# covid-respirator-ProtoB.net
KiCad netlist of a schematic drawn in EAGLE
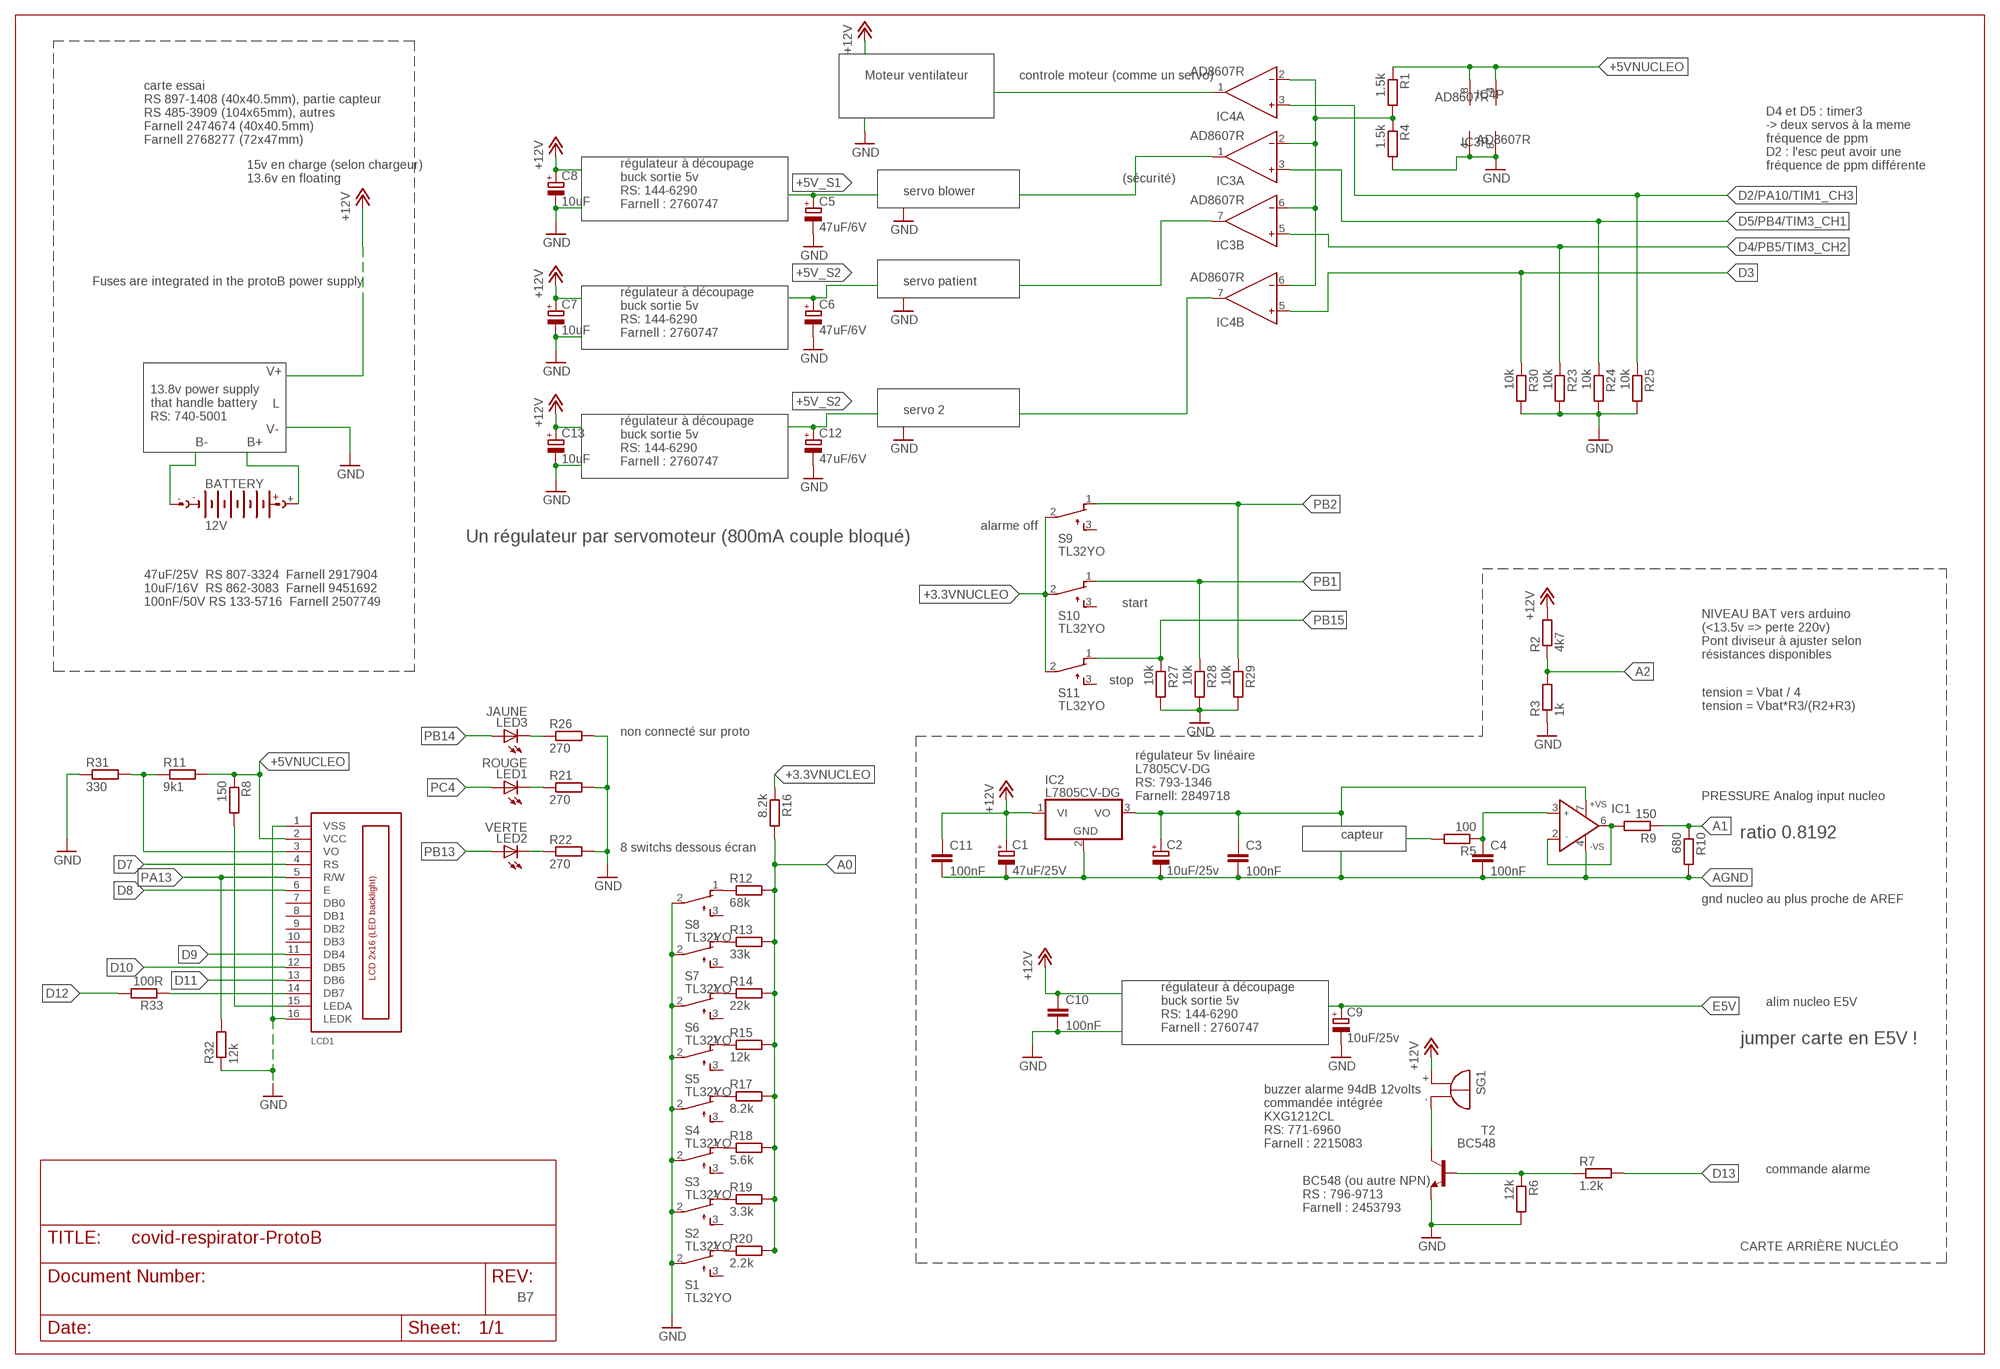
[diagram p0: schematic, sheet 1]

(export (version "E")
  (design (tool "Eeschema 10.0.6"))
  (components
    (comp (ref "BATTERY")
      (value "12V")
      (footprint "eagle-import:AB9V")
      (libsource (lib "eagle-import") (part "AB9V"))
    )
    (comp (ref "C1")
      (value "47uF/25V")
      (footprint "eagle-import:150CLZ-1010")
      (libsource (lib "eagle-import") (part "CPOL-EU150CLZ-1010"))
    )
    (comp (ref "C2")
      (value "10uF/25v")
      (footprint "eagle-import:150CLZ-1010")
      (libsource (lib "eagle-import") (part "CPOL-EU150CLZ-1010"))
    )
    (comp (ref "C3")
      (value "100nF")
      (footprint "eagle-import:C050-050X075")
      (libsource (lib "eagle-import") (part "C-EU050-050X075"))
    )
    (comp (ref "C4")
      (value "100nF")
      (footprint "eagle-import:C050-050X075")
      (libsource (lib "eagle-import") (part "C-EU050-050X075"))
    )
    (comp (ref "C5")
      (value "47uF/6V")
      (footprint "eagle-import:150CLZ-1010")
      (libsource (lib "eagle-import") (part "CPOL-EU150CLZ-1010"))
    )
    (comp (ref "C6")
      (value "47uF/6V")
      (footprint "eagle-import:150CLZ-1010")
      (libsource (lib "eagle-import") (part "CPOL-EU150CLZ-1010"))
    )
    (comp (ref "C7")
      (value "10uF")
      (footprint "eagle-import:150CLZ-1010")
      (libsource (lib "eagle-import") (part "CPOL-EU150CLZ-1010"))
    )
    (comp (ref "C8")
      (value "10uF")
      (footprint "eagle-import:150CLZ-1010")
      (libsource (lib "eagle-import") (part "CPOL-EU150CLZ-1010"))
    )
    (comp (ref "C9")
      (value "10uF/25v")
      (footprint "eagle-import:150CLZ-1010")
      (libsource (lib "eagle-import") (part "CPOL-EU150CLZ-1010"))
    )
    (comp (ref "C10")
      (value "100nF")
      (footprint "eagle-import:C050-050X075")
      (libsource (lib "eagle-import") (part "C-EU050-050X075"))
    )
    (comp (ref "C11")
      (value "100nF")
      (footprint "eagle-import:C050-050X075")
      (libsource (lib "eagle-import") (part "C-EU050-050X075"))
    )
    (comp (ref "C12")
      (value "47uF/6V")
      (footprint "eagle-import:150CLZ-1010")
      (libsource (lib "eagle-import") (part "CPOL-EU150CLZ-1010"))
    )
    (comp (ref "C13")
      (value "10uF")
      (footprint "eagle-import:150CLZ-1010")
      (libsource (lib "eagle-import") (part "CPOL-EU150CLZ-1010"))
    )
    (comp (ref "IC1")
      (value "AD825R")
      (footprint "eagle-import:SO8")
      (fields (field (name "MF") "ALTERA CORPORATION") (field (name "MPN") "AD825ARZ"))
      (libsource (lib "eagle-import") (part "AD825R"))
    )
    (comp (ref "IC2")
      (value "L7805CV-DG")
      (footprint "eagle-import:TO220H")
      (libsource (lib "eagle-import") (part "78T05"))
    )
    (comp (ref "IC3")
      (value "AD8607R")
      (footprint "eagle-import:SO8")
      (fields (field (name "MPN") "AD8607ARMZ-R2"))
      (libsource (lib "eagle-import") (part "AD8607R"))
    )
    (comp (ref "IC4")
      (value "AD8607R")
      (footprint "eagle-import:SO8")
      (fields (field (name "MPN") "AD8607ARMZ-R2"))
      (libsource (lib "eagle-import") (part "AD8607R"))
    )
    (comp (ref "LCD1")
      (value "LCD_2X16_SIL")
      (footprint "eagle-import:HY-1602F")
      (libsource (lib "eagle-import") (part "LCD_2X16_SIL"))
    )
    (comp (ref "LED1")
      (value "ROUGE")
      (footprint "eagle-import:LED3MM")
      (libsource (lib "eagle-import") (part "LED3MM"))
    )
    (comp (ref "LED2")
      (value "VERTE")
      (footprint "eagle-import:LED3MM")
      (libsource (lib "eagle-import") (part "LED3MM"))
    )
    (comp (ref "LED3")
      (value "JAUNE")
      (footprint "eagle-import:LED3MM")
      (libsource (lib "eagle-import") (part "LED3MM"))
    )
    (comp (ref "R1")
      (value "1.5k")
      (footprint "eagle-import:0207_10")
      (libsource (lib "eagle-import") (part "R-EU_0207/10"))
    )
    (comp (ref "R2")
      (value "4k7")
      (footprint "eagle-import:0207_10")
      (libsource (lib "eagle-import") (part "R-EU_0207/10"))
    )
    (comp (ref "R3")
      (value "1k")
      (footprint "eagle-import:0207_10")
      (libsource (lib "eagle-import") (part "R-EU_0207/10"))
    )
    (comp (ref "R4")
      (value "1.5k")
      (footprint "eagle-import:0207_10")
      (libsource (lib "eagle-import") (part "R-EU_0207/10"))
    )
    (comp (ref "R5")
      (value "100")
      (footprint "eagle-import:0207_10")
      (libsource (lib "eagle-import") (part "R-EU_0207/10"))
    )
    (comp (ref "R6")
      (value "12k")
      (footprint "eagle-import:0207_10")
      (libsource (lib "eagle-import") (part "R-EU_0207/10"))
    )
    (comp (ref "R7")
      (value "1.2k")
      (footprint "eagle-import:0207_10")
      (libsource (lib "eagle-import") (part "R-EU_0207/10"))
    )
    (comp (ref "R8")
      (value "150")
      (footprint "eagle-import:0207_10")
      (libsource (lib "eagle-import") (part "R-EU_0207/10"))
    )
    (comp (ref "R9")
      (value "150")
      (footprint "eagle-import:0207_10")
      (libsource (lib "eagle-import") (part "R-EU_0207/10"))
    )
    (comp (ref "R10")
      (value "680")
      (footprint "eagle-import:0207_10")
      (libsource (lib "eagle-import") (part "R-EU_0207/10"))
    )
    (comp (ref "R11")
      (value "9k1")
      (footprint "eagle-import:0207_10")
      (libsource (lib "eagle-import") (part "R-EU_0207/10"))
    )
    (comp (ref "R12")
      (value "68k")
      (footprint "eagle-import:0207_10")
      (libsource (lib "eagle-import") (part "R-EU_0207/10"))
    )
    (comp (ref "R13")
      (value "33k")
      (footprint "eagle-import:0207_10")
      (libsource (lib "eagle-import") (part "R-EU_0207/10"))
    )
    (comp (ref "R14")
      (value "22k")
      (footprint "eagle-import:0207_10")
      (libsource (lib "eagle-import") (part "R-EU_0207/10"))
    )
    (comp (ref "R15")
      (value "12k")
      (footprint "eagle-import:0207_10")
      (libsource (lib "eagle-import") (part "R-EU_0207/10"))
    )
    (comp (ref "R16")
      (value "8.2k")
      (footprint "eagle-import:0207_10")
      (libsource (lib "eagle-import") (part "R-EU_0207/10"))
    )
    (comp (ref "R17")
      (value "8.2k")
      (footprint "eagle-import:0207_10")
      (libsource (lib "eagle-import") (part "R-EU_0207/10"))
    )
    (comp (ref "R18")
      (value "5.6k")
      (footprint "eagle-import:0207_10")
      (libsource (lib "eagle-import") (part "R-EU_0207/10"))
    )
    (comp (ref "R19")
      (value "3.3k")
      (footprint "eagle-import:0207_10")
      (libsource (lib "eagle-import") (part "R-EU_0207/10"))
    )
    (comp (ref "R20")
      (value "2.2k")
      (footprint "eagle-import:0207_10")
      (libsource (lib "eagle-import") (part "R-EU_0207/10"))
    )
    (comp (ref "R21")
      (value "270")
      (footprint "eagle-import:0207_10")
      (libsource (lib "eagle-import") (part "R-EU_0207/10"))
    )
    (comp (ref "R22")
      (value "270")
      (footprint "eagle-import:0207_10")
      (libsource (lib "eagle-import") (part "R-EU_0207/10"))
    )
    (comp (ref "R23")
      (value "10k")
      (footprint "eagle-import:0207_10")
      (libsource (lib "eagle-import") (part "R-EU_0207/10"))
    )
    (comp (ref "R24")
      (value "10k")
      (footprint "eagle-import:0207_10")
      (libsource (lib "eagle-import") (part "R-EU_0207/10"))
    )
    (comp (ref "R25")
      (value "10k")
      (footprint "eagle-import:0207_10")
      (libsource (lib "eagle-import") (part "R-EU_0207/10"))
    )
    (comp (ref "R26")
      (value "270")
      (footprint "eagle-import:0207_10")
      (libsource (lib "eagle-import") (part "R-EU_0207/10"))
    )
    (comp (ref "R27")
      (value "10k")
      (footprint "eagle-import:0207_10")
      (libsource (lib "eagle-import") (part "R-EU_0207/10"))
    )
    (comp (ref "R28")
      (value "10k")
      (footprint "eagle-import:0207_10")
      (libsource (lib "eagle-import") (part "R-EU_0207/10"))
    )
    (comp (ref "R29")
      (value "10k")
      (footprint "eagle-import:0207_10")
      (libsource (lib "eagle-import") (part "R-EU_0207/10"))
    )
    (comp (ref "R30")
      (value "10k")
      (footprint "eagle-import:0207_10")
      (libsource (lib "eagle-import") (part "R-EU_0207/10"))
    )
    (comp (ref "R31")
      (value "330")
      (footprint "eagle-import:0207_10")
      (libsource (lib "eagle-import") (part "R-EU_0207/10"))
    )
    (comp (ref "R32")
      (value "12k")
      (footprint "eagle-import:0207_10")
      (libsource (lib "eagle-import") (part "R-EU_0207/10"))
    )
    (comp (ref "R33")
      (value "100R")
      (footprint "eagle-import:0207_10")
      (libsource (lib "eagle-import") (part "R-EU_0207/10"))
    )
    (comp (ref "S1")
      (value "TL32YO")
      (footprint "eagle-import:TL3XYO")
      (libsource (lib "eagle-import") (part "TL32YO"))
    )
    (comp (ref "S2")
      (value "TL32YO")
      (footprint "eagle-import:TL3XYO")
      (libsource (lib "eagle-import") (part "TL32YO"))
    )
    (comp (ref "S3")
      (value "TL32YO")
      (footprint "eagle-import:TL3XYO")
      (libsource (lib "eagle-import") (part "TL32YO"))
    )
    (comp (ref "S4")
      (value "TL32YO")
      (footprint "eagle-import:TL3XYO")
      (libsource (lib "eagle-import") (part "TL32YO"))
    )
    (comp (ref "S5")
      (value "TL32YO")
      (footprint "eagle-import:TL3XYO")
      (libsource (lib "eagle-import") (part "TL32YO"))
    )
    (comp (ref "S6")
      (value "TL32YO")
      (footprint "eagle-import:TL3XYO")
      (libsource (lib "eagle-import") (part "TL32YO"))
    )
    (comp (ref "S7")
      (value "TL32YO")
      (footprint "eagle-import:TL3XYO")
      (libsource (lib "eagle-import") (part "TL32YO"))
    )
    (comp (ref "S8")
      (value "TL32YO")
      (footprint "eagle-import:TL3XYO")
      (libsource (lib "eagle-import") (part "TL32YO"))
    )
    (comp (ref "S9")
      (value "TL32YO")
      (footprint "eagle-import:TL3XYO")
      (libsource (lib "eagle-import") (part "TL32YO"))
    )
    (comp (ref "S10")
      (value "TL32YO")
      (footprint "eagle-import:TL3XYO")
      (libsource (lib "eagle-import") (part "TL32YO"))
    )
    (comp (ref "S11")
      (value "TL32YO")
      (footprint "eagle-import:TL3XYO")
      (libsource (lib "eagle-import") (part "TL32YO"))
    )
    (comp (ref "SG1")
      (value "F/EB20P")
      (footprint "eagle-import:F_EB20P")
      (libsource (lib "eagle-import") (part "F/EB20P"))
    )
    (comp (ref "T2")
      (value "BC548")
      (footprint "eagle-import:TO92-CBE")
      (libsource (lib "eagle-import") (part "-NPN-TO92-CBEBC548"))
    )
  )
  (nets
    (net (code "1") (name "+3.3VNUCLEO") (class "Default")
      (node (ref "R16") (pin "1") (pinfunction "1_1") (pintype "passive"))
      (node (ref "S10") (pin "2") (pinfunction "P_2") (pintype "passive"))
      (node (ref "S11") (pin "2") (pinfunction "P_2") (pintype "passive"))
      (node (ref "S9") (pin "2") (pinfunction "P_2") (pintype "passive"))
    )
    (net (code "2") (name "+5VNUCLEO") (class "Default")
      (node (ref "IC3") (pin "4") (pinfunction "V-_4") (pintype "power_in"))
      (node (ref "IC4") (pin "8") (pinfunction "V+_8") (pintype "power_in"))
      (node (ref "LCD1") (pin "2") (pinfunction "VCC_2") (pintype "power_in"))
      (node (ref "R1") (pin "1") (pinfunction "1_1") (pintype "passive"))
      (node (ref "R11") (pin "2") (pinfunction "2_2") (pintype "passive"))
      (node (ref "R8") (pin "1") (pinfunction "1_1") (pintype "passive"))
    )
    (net (code "3") (name "+5V_S1") (class "Default")
      (node (ref "C5") (pin "+") (pinfunction "+_+") (pintype "passive"))
    )
    (net (code "4") (name "+5V_S2") (class "Default")
      (node (ref "C12") (pin "+") (pinfunction "+_+") (pintype "passive"))
      (node (ref "C6") (pin "+") (pinfunction "+_+") (pintype "passive"))
    )
    (net (code "5") (name "+12V") (class "Default")
      (node (ref "C1") (pin "+") (pinfunction "+_+") (pintype "passive"))
      (node (ref "C10") (pin "1") (pinfunction "1_1") (pintype "passive"))
      (node (ref "C11") (pin "1") (pinfunction "1_1") (pintype "passive"))
      (node (ref "C13") (pin "+") (pinfunction "+_+") (pintype "passive"))
      (node (ref "C7") (pin "+") (pinfunction "+_+") (pintype "passive"))
      (node (ref "C8") (pin "+") (pinfunction "+_+") (pintype "passive"))
      (node (ref "IC2") (pin "1") (pinfunction "VI_1") (pintype "input"))
      (node (ref "R2") (pin "2") (pinfunction "2_2") (pintype "passive"))
      (node (ref "SG1") (pin "+") (pinfunction "+_+") (pintype "passive"))
    )
    (net (code "6") (name "A0") (class "Default")
      (node (ref "R12") (pin "2") (pinfunction "2_2") (pintype "passive"))
      (node (ref "R13") (pin "2") (pinfunction "2_2") (pintype "passive"))
      (node (ref "R14") (pin "2") (pinfunction "2_2") (pintype "passive"))
      (node (ref "R15") (pin "2") (pinfunction "2_2") (pintype "passive"))
      (node (ref "R16") (pin "2") (pinfunction "2_2") (pintype "passive"))
      (node (ref "R17") (pin "2") (pinfunction "2_2") (pintype "passive"))
      (node (ref "R18") (pin "2") (pinfunction "2_2") (pintype "passive"))
      (node (ref "R19") (pin "2") (pinfunction "2_2") (pintype "passive"))
      (node (ref "R20") (pin "2") (pinfunction "2_2") (pintype "passive"))
    )
    (net (code "7") (name "A1") (class "Default")
      (node (ref "R10") (pin "1") (pinfunction "1_1") (pintype "passive"))
      (node (ref "R9") (pin "1") (pinfunction "1_1") (pintype "passive"))
    )
    (net (code "8") (name "A2") (class "Default")
      (node (ref "R2") (pin "1") (pinfunction "1_1") (pintype "passive"))
      (node (ref "R3") (pin "2") (pinfunction "2_2") (pintype "passive"))
    )
    (net (code "9") (name "AGND") (class "Default")
      (node (ref "C1") (pin "-") (pinfunction "-_-") (pintype "passive"))
      (node (ref "C11") (pin "2") (pinfunction "2_2") (pintype "passive"))
      (node (ref "C2") (pin "-") (pinfunction "-_-") (pintype "passive"))
      (node (ref "C3") (pin "2") (pinfunction "2_2") (pintype "passive"))
      (node (ref "C4") (pin "2") (pinfunction "2_2") (pintype "passive"))
      (node (ref "IC1") (pin "4") (pinfunction "-VS_4") (pintype "input"))
      (node (ref "IC2") (pin "2") (pinfunction "GND_2") (pintype "passive"))
      (node (ref "R10") (pin "2") (pinfunction "2_2") (pintype "passive"))
    )
    (net (code "10") (name "D2{slash}PA10{slash}TIM1_CH3") (class "Default")
      (node (ref "IC4") (pin "3") (pinfunction "IN+_3") (pintype "input"))
      (node (ref "R25") (pin "1") (pinfunction "1_1") (pintype "passive"))
    )
    (net (code "11") (name "D3") (class "Default")
      (node (ref "IC4") (pin "5") (pinfunction "IN+_5") (pintype "input"))
      (node (ref "R30") (pin "1") (pinfunction "1_1") (pintype "passive"))
    )
    (net (code "12") (name "D4{slash}PB5{slash}TIM3_CH2") (class "Default")
      (node (ref "IC3") (pin "5") (pinfunction "IN+_5") (pintype "input"))
      (node (ref "R23") (pin "1") (pinfunction "1_1") (pintype "passive"))
    )
    (net (code "13") (name "D5{slash}PB4{slash}TIM3_CH1") (class "Default")
      (node (ref "IC3") (pin "3") (pinfunction "IN+_3") (pintype "input"))
      (node (ref "R24") (pin "1") (pinfunction "1_1") (pintype "passive"))
    )
    (net (code "14") (name "D7") (class "Default")
      (node (ref "LCD1") (pin "4") (pinfunction "RS_4") (pintype "input"))
    )
    (net (code "15") (name "D8") (class "Default")
      (node (ref "LCD1") (pin "6") (pinfunction "E_6") (pintype "input"))
    )
    (net (code "16") (name "D9") (class "Default")
      (node (ref "LCD1") (pin "11") (pinfunction "DB4_11") (pintype "bidirectional"))
    )
    (net (code "17") (name "D10") (class "Default")
      (node (ref "LCD1") (pin "12") (pinfunction "DB5_12") (pintype "bidirectional"))
    )
    (net (code "18") (name "D11") (class "Default")
      (node (ref "LCD1") (pin "13") (pinfunction "DB6_13") (pintype "bidirectional"))
    )
    (net (code "19") (name "D12") (class "Default")
      (node (ref "R33") (pin "2") (pinfunction "2_2") (pintype "passive"))
    )
    (net (code "20") (name "D13") (class "Default")
      (node (ref "R7") (pin "2") (pinfunction "2_2") (pintype "passive"))
    )
    (net (code "21") (name "E5V") (class "Default")
      (node (ref "C9") (pin "+") (pinfunction "+_+") (pintype "passive"))
    )
    (net (code "22") (name "GND") (class "Default")
      (node (ref "C10") (pin "2") (pinfunction "2_2") (pintype "passive"))
      (node (ref "C12") (pin "-") (pinfunction "-_-") (pintype "passive"))
      (node (ref "C13") (pin "-") (pinfunction "-_-") (pintype "passive"))
      (node (ref "C5") (pin "-") (pinfunction "-_-") (pintype "passive"))
      (node (ref "C6") (pin "-") (pinfunction "-_-") (pintype "passive"))
      (node (ref "C7") (pin "-") (pinfunction "-_-") (pintype "passive"))
      (node (ref "C8") (pin "-") (pinfunction "-_-") (pintype "passive"))
      (node (ref "C9") (pin "-") (pinfunction "-_-") (pintype "passive"))
      (node (ref "IC3") (pin "8") (pinfunction "V+_8") (pintype "power_in"))
      (node (ref "IC4") (pin "4") (pinfunction "V-_4") (pintype "power_in"))
      (node (ref "LCD1") (pin "1") (pinfunction "VSS_1") (pintype "power_in"))
      (node (ref "LCD1") (pin "16") (pinfunction "LEDK_16") (pintype "passive"))
      (node (ref "R21") (pin "2") (pinfunction "2_2") (pintype "passive"))
      (node (ref "R22") (pin "2") (pinfunction "2_2") (pintype "passive"))
      (node (ref "R23") (pin "2") (pinfunction "2_2") (pintype "passive"))
      (node (ref "R24") (pin "2") (pinfunction "2_2") (pintype "passive"))
      (node (ref "R25") (pin "2") (pinfunction "2_2") (pintype "passive"))
      (node (ref "R26") (pin "2") (pinfunction "2_2") (pintype "passive"))
      (node (ref "R27") (pin "2") (pinfunction "2_2") (pintype "passive"))
      (node (ref "R28") (pin "2") (pinfunction "2_2") (pintype "passive"))
      (node (ref "R29") (pin "2") (pinfunction "2_2") (pintype "passive"))
      (node (ref "R3") (pin "1") (pinfunction "1_1") (pintype "passive"))
      (node (ref "R30") (pin "2") (pinfunction "2_2") (pintype "passive"))
      (node (ref "R31") (pin "1") (pinfunction "1_1") (pintype "passive"))
      (node (ref "R32") (pin "1") (pinfunction "1_1") (pintype "passive"))
      (node (ref "R4") (pin "2") (pinfunction "2_2") (pintype "passive"))
      (node (ref "R6") (pin "2") (pinfunction "2_2") (pintype "passive"))
      (node (ref "S1") (pin "2") (pinfunction "P_2") (pintype "passive"))
      (node (ref "S2") (pin "2") (pinfunction "P_2") (pintype "passive"))
      (node (ref "S3") (pin "2") (pinfunction "P_2") (pintype "passive"))
      (node (ref "S4") (pin "2") (pinfunction "P_2") (pintype "passive"))
      (node (ref "S5") (pin "2") (pinfunction "P_2") (pintype "passive"))
      (node (ref "S6") (pin "2") (pinfunction "P_2") (pintype "passive"))
      (node (ref "S7") (pin "2") (pinfunction "P_2") (pintype "passive"))
      (node (ref "S8") (pin "2") (pinfunction "P_2") (pintype "passive"))
      (node (ref "T2") (pin "E") (pinfunction "E_E") (pintype "passive"))
    )
    (net (code "23") (name "Net-(IC1-+VS)") (class "Default")
      (node (ref "C2") (pin "+") (pinfunction "+_+") (pintype "passive"))
      (node (ref "C3") (pin "1") (pinfunction "1_1") (pintype "passive"))
      (node (ref "IC1") (pin "7") (pinfunction "+VS_7") (pintype "input"))
      (node (ref "IC2") (pin "3") (pinfunction "VO_3") (pintype "passive"))
    )
    (net (code "24") (name "Net-(IC1-IN+)") (class "Default")
      (node (ref "C4") (pin "1") (pinfunction "1_1") (pintype "passive"))
      (node (ref "IC1") (pin "3") (pinfunction "IN+_3") (pintype "input"))
      (node (ref "R5") (pin "1") (pinfunction "1_1") (pintype "passive"))
    )
    (net (code "25") (name "Net-(IC1-IN-)") (class "Default")
      (node (ref "IC1") (pin "2") (pinfunction "IN-_2") (pintype "input"))
      (node (ref "IC1") (pin "6") (pinfunction "OUT_6") (pintype "output"))
      (node (ref "R9") (pin "2") (pinfunction "2_2") (pintype "passive"))
    )
    (net (code "26") (name "Net-(IC3A-IN-)") (class "Default")
      (node (ref "IC3") (pin "2") (pinfunction "IN-_2") (pintype "input"))
      (node (ref "IC3") (pin "6") (pinfunction "IN-_6") (pintype "input"))
      (node (ref "IC4") (pin "2") (pinfunction "IN-_2") (pintype "input"))
      (node (ref "IC4") (pin "6") (pinfunction "IN-_6") (pintype "input"))
      (node (ref "R1") (pin "2") (pinfunction "2_2") (pintype "passive"))
      (node (ref "R4") (pin "1") (pinfunction "1_1") (pintype "passive"))
    )
    (net (code "27") (name "Net-(LCD1-DB7)") (class "Default")
      (node (ref "LCD1") (pin "14") (pinfunction "DB7_14") (pintype "bidirectional"))
      (node (ref "R33") (pin "1") (pinfunction "1_1") (pintype "passive"))
    )
    (net (code "28") (name "Net-(LCD1-LEDA)") (class "Default")
      (node (ref "LCD1") (pin "15") (pinfunction "LEDA_15") (pintype "passive"))
      (node (ref "R8") (pin "2") (pinfunction "2_2") (pintype "passive"))
    )
    (net (code "29") (name "Net-(LCD1-VO)") (class "Default")
      (node (ref "LCD1") (pin "3") (pinfunction "VO_3") (pintype "input"))
      (node (ref "R11") (pin "1") (pinfunction "1_1") (pintype "passive"))
      (node (ref "R31") (pin "2") (pinfunction "2_2") (pintype "passive"))
    )
    (net (code "30") (name "Net-(LED1-C)") (class "Default")
      (node (ref "LED1") (pin "K") (pinfunction "C_K") (pintype "passive"))
      (node (ref "R21") (pin "1") (pinfunction "1_1") (pintype "passive"))
    )
    (net (code "31") (name "Net-(LED2-C)") (class "Default")
      (node (ref "LED2") (pin "K") (pinfunction "C_K") (pintype "passive"))
      (node (ref "R22") (pin "1") (pinfunction "1_1") (pintype "passive"))
    )
    (net (code "32") (name "Net-(LED3-C)") (class "Default")
      (node (ref "LED3") (pin "K") (pinfunction "C_K") (pintype "passive"))
      (node (ref "R26") (pin "1") (pinfunction "1_1") (pintype "passive"))
    )
    (net (code "33") (name "Net-(R6-Pad1)") (class "Default")
      (node (ref "R6") (pin "1") (pinfunction "1_1") (pintype "passive"))
      (node (ref "R7") (pin "1") (pinfunction "1_1") (pintype "passive"))
      (node (ref "T2") (pin "B") (pinfunction "B_B") (pintype "passive"))
    )
    (net (code "34") (name "Net-(S1-O)") (class "Default")
      (node (ref "R20") (pin "1") (pinfunction "1_1") (pintype "passive"))
      (node (ref "S1") (pin "1") (pinfunction "O_1") (pintype "passive"))
    )
    (net (code "35") (name "Net-(S2-O)") (class "Default")
      (node (ref "R19") (pin "1") (pinfunction "1_1") (pintype "passive"))
      (node (ref "S2") (pin "1") (pinfunction "O_1") (pintype "passive"))
    )
    (net (code "36") (name "Net-(S3-O)") (class "Default")
      (node (ref "R18") (pin "1") (pinfunction "1_1") (pintype "passive"))
      (node (ref "S3") (pin "1") (pinfunction "O_1") (pintype "passive"))
    )
    (net (code "37") (name "Net-(S4-O)") (class "Default")
      (node (ref "R17") (pin "1") (pinfunction "1_1") (pintype "passive"))
      (node (ref "S4") (pin "1") (pinfunction "O_1") (pintype "passive"))
    )
    (net (code "38") (name "Net-(S5-O)") (class "Default")
      (node (ref "R15") (pin "1") (pinfunction "1_1") (pintype "passive"))
      (node (ref "S5") (pin "1") (pinfunction "O_1") (pintype "passive"))
    )
    (net (code "39") (name "Net-(S6-O)") (class "Default")
      (node (ref "R14") (pin "1") (pinfunction "1_1") (pintype "passive"))
      (node (ref "S6") (pin "1") (pinfunction "O_1") (pintype "passive"))
    )
    (net (code "40") (name "Net-(S7-O)") (class "Default")
      (node (ref "R13") (pin "1") (pinfunction "1_1") (pintype "passive"))
      (node (ref "S7") (pin "1") (pinfunction "O_1") (pintype "passive"))
    )
    (net (code "41") (name "Net-(S8-O)") (class "Default")
      (node (ref "R12") (pin "1") (pinfunction "1_1") (pintype "passive"))
      (node (ref "S8") (pin "1") (pinfunction "O_1") (pintype "passive"))
    )
    (net (code "42") (name "Net-(SG1-Pad-)") (class "Default")
      (node (ref "SG1") (pin "-") (pinfunction "-_-") (pintype "passive"))
      (node (ref "T2") (pin "C") (pinfunction "C_C") (pintype "passive"))
    )
    (net (code "43") (name "PA13") (class "Default")
      (node (ref "LCD1") (pin "5") (pinfunction "R/W_5") (pintype "input"))
      (node (ref "R32") (pin "2") (pinfunction "2_2") (pintype "passive"))
    )
    (net (code "44") (name "PB1") (class "Default")
      (node (ref "R28") (pin "1") (pinfunction "1_1") (pintype "passive"))
      (node (ref "S10") (pin "1") (pinfunction "O_1") (pintype "passive"))
    )
    (net (code "45") (name "PB2") (class "Default")
      (node (ref "R29") (pin "1") (pinfunction "1_1") (pintype "passive"))
      (node (ref "S9") (pin "1") (pinfunction "O_1") (pintype "passive"))
    )
    (net (code "46") (name "PB13") (class "Default")
      (node (ref "LED2") (pin "A") (pinfunction "A_A") (pintype "passive"))
    )
    (net (code "47") (name "PB14") (class "Default")
      (node (ref "LED3") (pin "A") (pinfunction "A_A") (pintype "passive"))
    )
    (net (code "48") (name "PB15") (class "Default")
      (node (ref "R27") (pin "1") (pinfunction "1_1") (pintype "passive"))
      (node (ref "S11") (pin "1") (pinfunction "O_1") (pintype "passive"))
    )
    (net (code "49") (name "PC4") (class "Default")
      (node (ref "LED1") (pin "A") (pinfunction "A_A") (pintype "passive"))
    )
    (net (code "50") (name "unconnected-(BATTERY-Pad+)") (class "Default")
      (node (ref "BATTERY") (pin "+") (pinfunction "+_+") (pintype "passive"))
    )
    (net (code "51") (name "unconnected-(BATTERY-Pad-)") (class "Default")
      (node (ref "BATTERY") (pin "-") (pinfunction "-_-") (pintype "passive"))
    )
    (net (code "52") (name "unconnected-(IC3A-OUT-Pad1)") (class "Default")
      (node (ref "IC3") (pin "1") (pinfunction "OUT_1") (pintype "output"))
    )
    (net (code "53") (name "unconnected-(IC3B-OUT-Pad7)") (class "Default")
      (node (ref "IC3") (pin "7") (pinfunction "OUT_7") (pintype "output"))
    )
    (net (code "54") (name "unconnected-(IC4A-OUT-Pad1)") (class "Default")
      (node (ref "IC4") (pin "1") (pinfunction "OUT_1") (pintype "output"))
    )
    (net (code "55") (name "unconnected-(IC4B-OUT-Pad7)") (class "Default")
      (node (ref "IC4") (pin "7") (pinfunction "OUT_7") (pintype "output"))
    )
    (net (code "56") (name "unconnected-(LCD1-DB0-Pad7)") (class "Default")
      (node (ref "LCD1") (pin "7") (pinfunction "DB0_7") (pintype "bidirectional"))
    )
    (net (code "57") (name "unconnected-(LCD1-DB1-Pad8)") (class "Default")
      (node (ref "LCD1") (pin "8") (pinfunction "DB1_8") (pintype "bidirectional"))
    )
    (net (code "58") (name "unconnected-(LCD1-DB2-Pad9)") (class "Default")
      (node (ref "LCD1") (pin "9") (pinfunction "DB2_9") (pintype "bidirectional"))
    )
    (net (code "59") (name "unconnected-(LCD1-DB3-Pad10)") (class "Default")
      (node (ref "LCD1") (pin "10") (pinfunction "DB3_10") (pintype "bidirectional"))
    )
    (net (code "60") (name "unconnected-(R5-Pad2)") (class "Default")
      (node (ref "R5") (pin "2") (pinfunction "2_2") (pintype "passive"))
    )
    (net (code "61") (name "unconnected-(S1-S-Pad3)") (class "Default")
      (node (ref "S1") (pin "3") (pinfunction "S_3") (pintype "passive"))
    )
    (net (code "62") (name "unconnected-(S2-S-Pad3)") (class "Default")
      (node (ref "S2") (pin "3") (pinfunction "S_3") (pintype "passive"))
    )
    (net (code "63") (name "unconnected-(S3-S-Pad3)") (class "Default")
      (node (ref "S3") (pin "3") (pinfunction "S_3") (pintype "passive"))
    )
    (net (code "64") (name "unconnected-(S4-S-Pad3)") (class "Default")
      (node (ref "S4") (pin "3") (pinfunction "S_3") (pintype "passive"))
    )
    (net (code "65") (name "unconnected-(S5-S-Pad3)") (class "Default")
      (node (ref "S5") (pin "3") (pinfunction "S_3") (pintype "passive"))
    )
    (net (code "66") (name "unconnected-(S6-S-Pad3)") (class "Default")
      (node (ref "S6") (pin "3") (pinfunction "S_3") (pintype "passive"))
    )
    (net (code "67") (name "unconnected-(S7-S-Pad3)") (class "Default")
      (node (ref "S7") (pin "3") (pinfunction "S_3") (pintype "passive"))
    )
    (net (code "68") (name "unconnected-(S8-S-Pad3)") (class "Default")
      (node (ref "S8") (pin "3") (pinfunction "S_3") (pintype "passive"))
    )
    (net (code "69") (name "unconnected-(S9-S-Pad3)") (class "Default")
      (node (ref "S9") (pin "3") (pinfunction "S_3") (pintype "passive"))
    )
    (net (code "70") (name "unconnected-(S10-S-Pad3)") (class "Default")
      (node (ref "S10") (pin "3") (pinfunction "S_3") (pintype "passive"))
    )
    (net (code "71") (name "unconnected-(S11-S-Pad3)") (class "Default")
      (node (ref "S11") (pin "3") (pinfunction "S_3") (pintype "passive"))
    )
  )
)
